# BLL-EBOOK.net
KiCad netlist of a schematic drawn in EAGLE
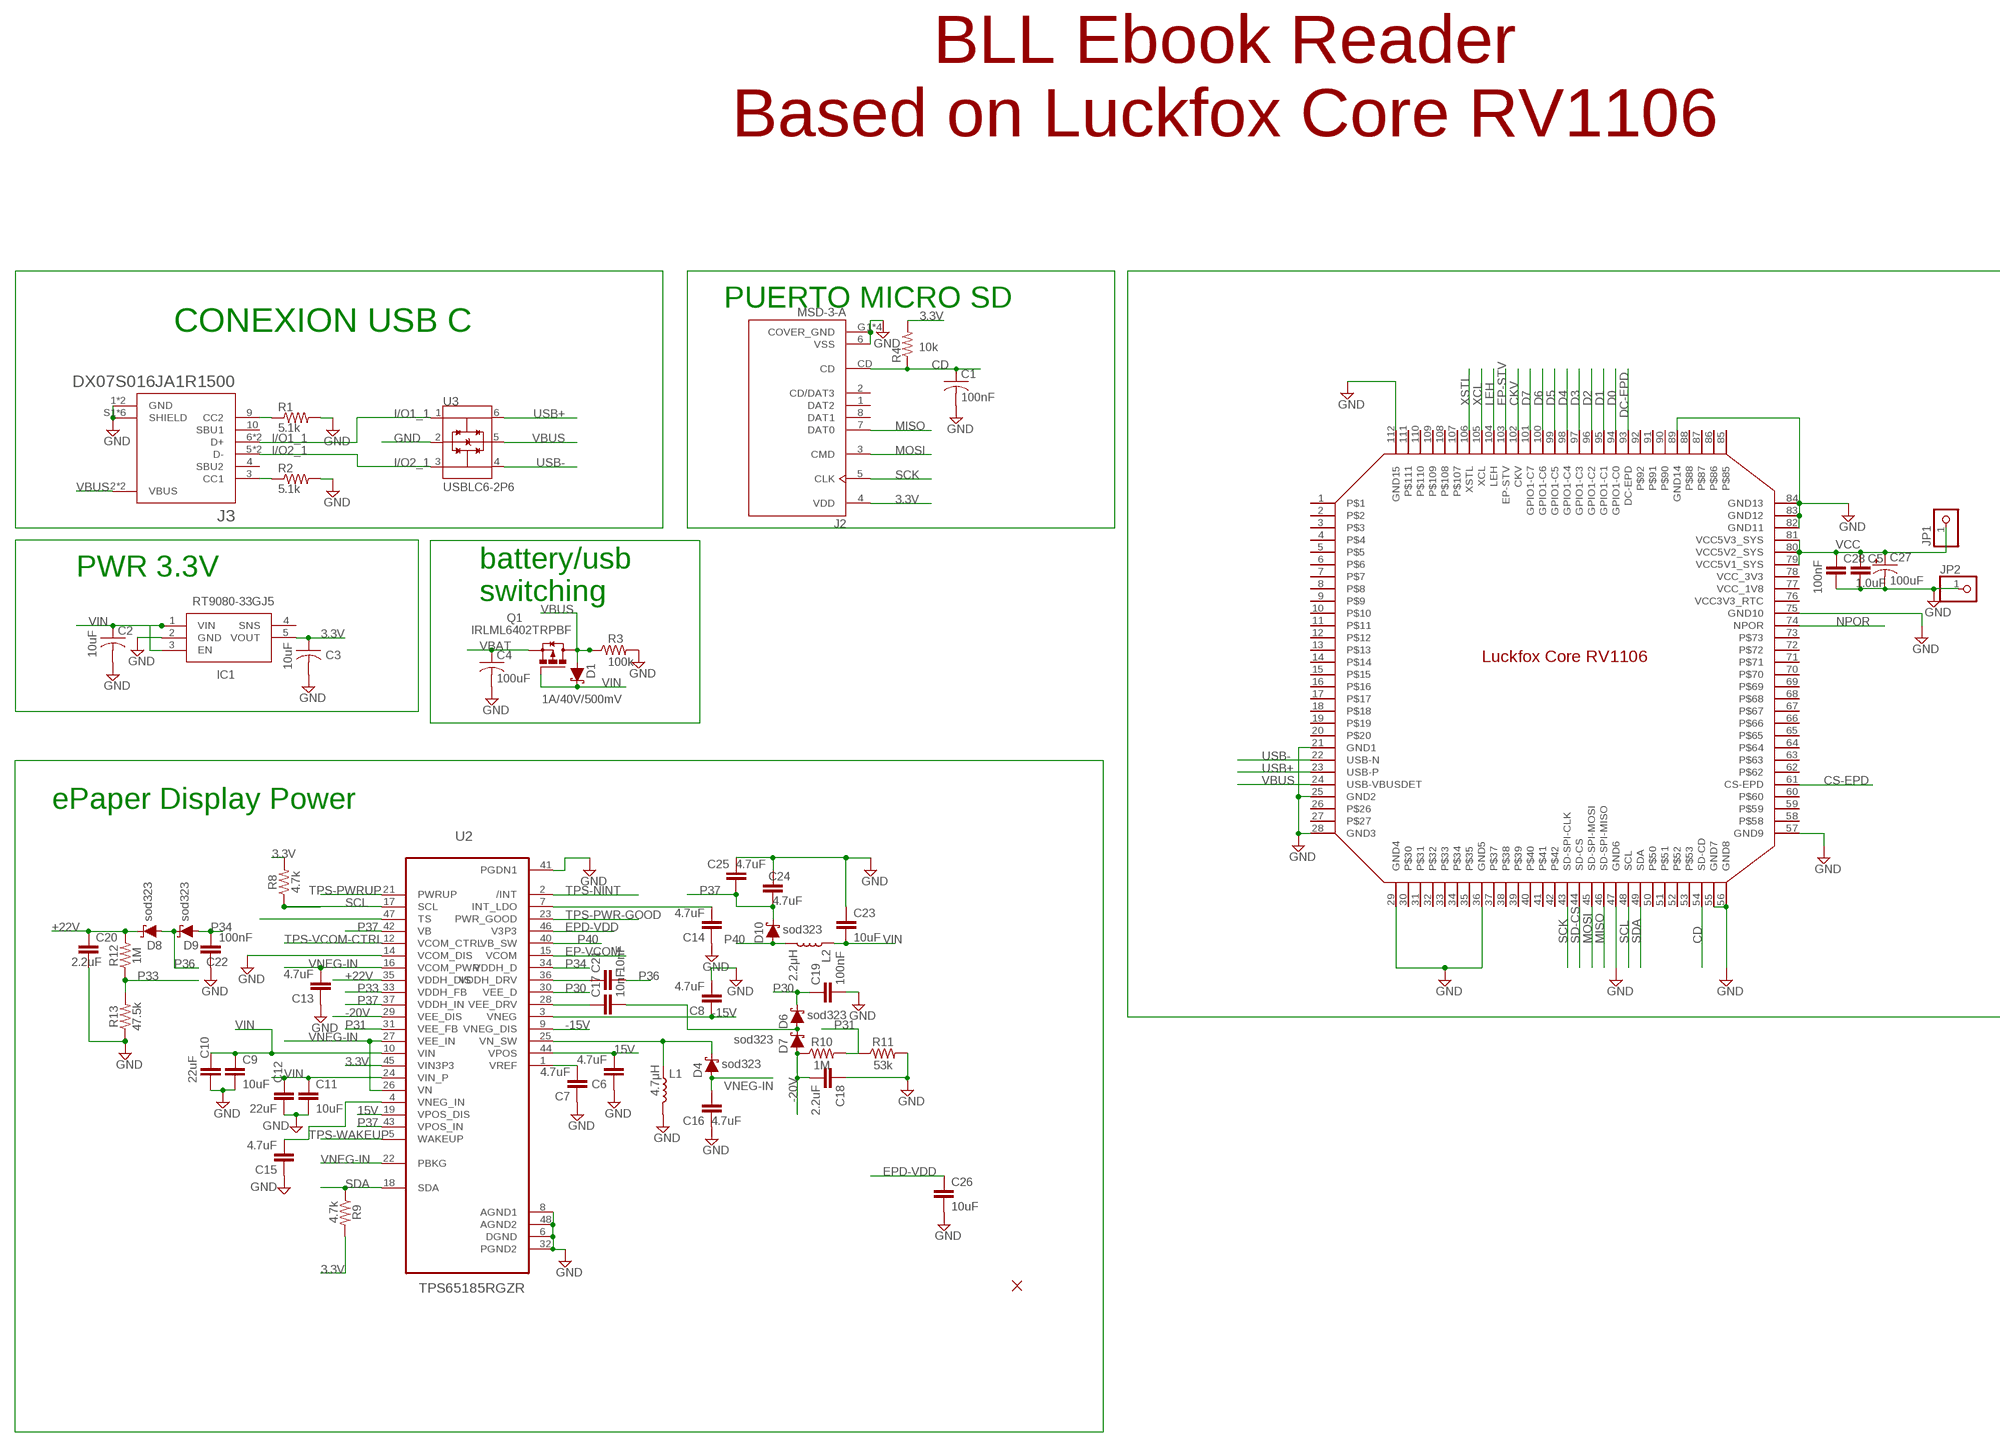
[diagram p0: schematic, sheet 1, part 1 of 2]
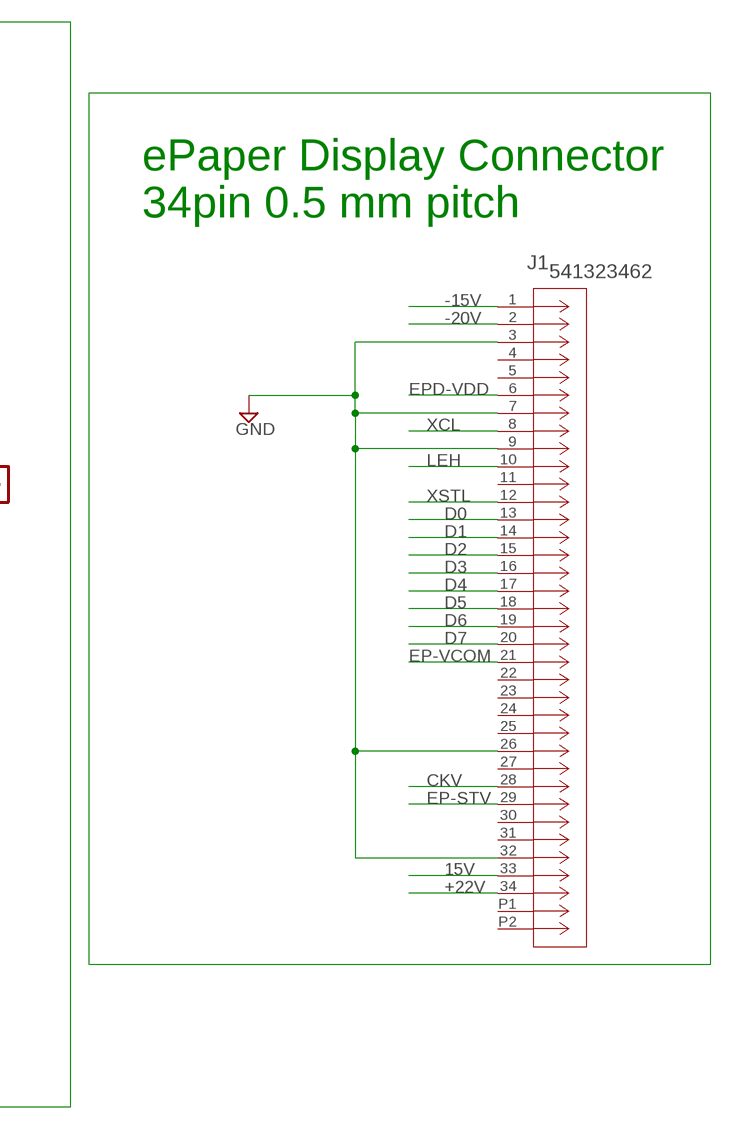
[diagram p1: schematic, sheet 1, part 2 of 2]

(export (version "E")
  (design (tool "Eeschema 10.0.6"))
  (components
    (comp (ref "C1")
      (value "100nF")
      (footprint "eagle-import:C0603")
      (libsource (lib "eagle-import") (part "C-USC0603"))
    )
    (comp (ref "C2")
      (value "10uF")
      (footprint "eagle-import:C0603")
      (libsource (lib "eagle-import") (part "C-USC0603"))
    )
    (comp (ref "C3")
      (value "10uF")
      (footprint "eagle-import:C0603")
      (libsource (lib "eagle-import") (part "C-USC0603"))
    )
    (comp (ref "C4")
      (value "100uF")
      (footprint "eagle-import:C0603")
      (libsource (lib "eagle-import") (part "C-USC0603"))
    )
    (comp (ref "C5")
      (value "1.0uF")
      (footprint "eagle-import:0603")
      (libsource (lib "eagle-import") (part "1.0UF-0603-16V-10%-X7R"))
    )
    (comp (ref "C6")
      (value "4.7uF")
      (footprint "eagle-import:0603")
      (libsource (lib "eagle-import") (part "4.7UF-0603-35V-(20%)"))
    )
    (comp (ref "C7")
      (value "4.7uF")
      (footprint "eagle-import:0603")
      (libsource (lib "eagle-import") (part "4.7UF-0603-35V-(20%)"))
    )
    (comp (ref "C8")
      (value "4.7uF")
      (footprint "eagle-import:0603")
      (libsource (lib "eagle-import") (part "4.7UF-0603-35V-(20%)"))
    )
    (comp (ref "C9")
      (value "10uF")
      (footprint "eagle-import:0805")
      (libsource (lib "eagle-import") (part "10UF-0805-10V-10%"))
    )
    (comp (ref "C10")
      (value "22uF")
      (footprint "eagle-import:0805")
      (libsource (lib "eagle-import") (part "22UF-0805-16V-20%"))
    )
    (comp (ref "C11")
      (value "10uF")
      (footprint "eagle-import:0805")
      (libsource (lib "eagle-import") (part "10UF-0805-10V-10%"))
    )
    (comp (ref "C12")
      (value "22uF")
      (footprint "eagle-import:0805")
      (libsource (lib "eagle-import") (part "22UF-0805-16V-20%"))
    )
    (comp (ref "C13")
      (value "4.7uF")
      (footprint "eagle-import:0603")
      (libsource (lib "eagle-import") (part "4.7UF-0603-35V-(20%)"))
    )
    (comp (ref "C14")
      (value "4.7uF")
      (footprint "eagle-import:0603")
      (libsource (lib "eagle-import") (part "4.7UF-0603-35V-(20%)"))
    )
    (comp (ref "C15")
      (value "4.7uF")
      (footprint "eagle-import:0603")
      (libsource (lib "eagle-import") (part "4.7UF-0603-35V-(20%)"))
    )
    (comp (ref "C16")
      (value "4.7uF")
      (footprint "eagle-import:0603")
      (libsource (lib "eagle-import") (part "4.7UF-0603-35V-(20%)"))
    )
    (comp (ref "C17")
      (value "10nF")
      (footprint "eagle-import:0603")
      (libsource (lib "eagle-import") (part "10NF-0603-50V-10%"))
    )
    (comp (ref "C18")
      (value "2.2uF")
      (footprint "eagle-import:1206")
      (libsource (lib "eagle-import") (part "2.2UF-1206-50V-10%"))
    )
    (comp (ref "C19")
      (value "100nF")
      (footprint "eagle-import:0603")
      (libsource (lib "eagle-import") (part "DNP-0603"))
    )
    (comp (ref "C20")
      (value "2.2uF")
      (footprint "eagle-import:1206")
      (libsource (lib "eagle-import") (part "2.2UF-1206-50V-10%"))
    )
    (comp (ref "C21")
      (value "10nF")
      (footprint "eagle-import:0603")
      (libsource (lib "eagle-import") (part "10NF-0603-50V-10%"))
    )
    (comp (ref "C22")
      (value "100nF")
      (footprint "eagle-import:0603")
      (libsource (lib "eagle-import") (part "DNP-0603"))
    )
    (comp (ref "C23")
      (value "10uF")
      (footprint "eagle-import:0805")
      (libsource (lib "eagle-import") (part "10UF-0805-10V-10%"))
    )
    (comp (ref "C24")
      (value "4.7uF")
      (footprint "eagle-import:0603")
      (libsource (lib "eagle-import") (part "4.7UF-0603-35V-(20%)"))
    )
    (comp (ref "C25")
      (value "4.7uF")
      (footprint "eagle-import:0603")
      (libsource (lib "eagle-import") (part "4.7UF-0603-35V-(20%)"))
    )
    (comp (ref "C26")
      (value "10uF")
      (footprint "eagle-import:0805")
      (libsource (lib "eagle-import") (part "10UF-0805-10V-10%"))
    )
    (comp (ref "C27")
      (value "100uF")
      (footprint "eagle-import:EIA3528")
      (libsource (lib "eagle-import") (part "100UF-POLAR-EIA3528-10V-20%(TANT)"))
    )
    (comp (ref "C28")
      (value "100nF")
      (footprint "eagle-import:0805")
      (libsource (lib "eagle-import") (part "CAP-0805"))
    )
    (comp (ref "D1")
      (value "1A/40V/500mV")
      (footprint "eagle-import:SMA-DIODE")
      (libsource (lib "eagle-import") (part "DIODE-SCHOTTKY-SS14"))
    )
    (comp (ref "D4")
      (value "sod323")
      (footprint "eagle-import:SOD-323")
      (libsource (lib "eagle-import") (part "DIODE-SCHOTTKY-PMEG4005EJ"))
    )
    (comp (ref "D6")
      (value "sod323")
      (footprint "eagle-import:SOD-323")
      (libsource (lib "eagle-import") (part "DIODE-SCHOTTKY-PMEG4005EJ"))
    )
    (comp (ref "D7")
      (value "sod323")
      (footprint "eagle-import:SOD-323")
      (libsource (lib "eagle-import") (part "DIODE-SCHOTTKY-PMEG4005EJ"))
    )
    (comp (ref "D8")
      (value "sod323")
      (footprint "eagle-import:SOD-323")
      (libsource (lib "eagle-import") (part "DIODE-SCHOTTKY-PMEG4005EJ"))
    )
    (comp (ref "D9")
      (value "sod323")
      (footprint "eagle-import:SOD-323")
      (libsource (lib "eagle-import") (part "DIODE-SCHOTTKY-PMEG4005EJ"))
    )
    (comp (ref "D10")
      (value "sod323")
      (footprint "eagle-import:SOD-323")
      (libsource (lib "eagle-import") (part "DIODE-SCHOTTKY-PMEG4005EJ"))
    )
    (comp (ref "IC1")
      (value "RT9080-33GJ5")
      (footprint "eagle-import:SOT94P280X100-5N")
      (fields (field (name "MF") "Richtek USA"))
      (libsource (lib "eagle-import") (part "RT9080-33GJ5"))
    )
    (comp (ref "J1")
      (value "541323462")
      (footprint "eagle-import:CON_541323462_MOL")
      (fields (field (name "MF") "Molex"))
      (libsource (lib "eagle-import") (part "541323462"))
    )
    (comp (ref "J2")
      (value "MSD-3-A")
      (footprint "eagle-import:CUI_MSD-3-A")
      (fields (field (name "MF") "Same Sky"))
      (libsource (lib "eagle-import") (part "MSD-3-A"))
    )
    (comp (ref "J3")
      (value "DX07S016JA1R1500")
      (footprint "eagle-import:JAE_DX07S016JA1R1500")
      (fields (field (name "MF") "JAE Electronics"))
      (libsource (lib "eagle-import") (part "DX07S016JA1R1500"))
    )
    (comp (ref "JP1")
      (value "PINHD-1X1")
      (footprint "eagle-import:1X01")
      (libsource (lib "eagle-import") (part "PINHD-1X1"))
    )
    (comp (ref "JP2")
      (value "PINHD-1X1")
      (footprint "eagle-import:1X01")
      (libsource (lib "eagle-import") (part "PINHD-1X1"))
    )
    (comp (ref "L1")
      (value "4.7μH")
      (footprint "eagle-import:1008(2520)")
      (libsource (lib "eagle-import") (part "4.7μH_SHIELDED_INDUCTOR"))
    )
    (comp (ref "L2")
      (value "2.2μH")
      (footprint "eagle-import:0806")
      (libsource (lib "eagle-import") (part "2.2μH_SHIELDED_INDUCTOR"))
    )
    (comp (ref "Q1")
      (value "IRLML6402TRPBF")
      (footprint "eagle-import:SOT23")
      (fields (field (name "MF") "Infineon Technologies") (field (name "MP") "IRLML6402"))
      (libsource (lib "eagle-import") (part "IRLML6402TRPBF"))
    )
    (comp (ref "R1")
      (value "5.1k")
      (footprint "eagle-import:M0805")
      (libsource (lib "eagle-import") (part "R-US_M0805"))
    )
    (comp (ref "R2")
      (value "5.1k")
      (footprint "eagle-import:M0805")
      (libsource (lib "eagle-import") (part "R-US_M0805"))
    )
    (comp (ref "R3")
      (value "100k")
      (footprint "eagle-import:R0603")
      (libsource (lib "eagle-import") (part "R-US_R0603"))
    )
    (comp (ref "R4")
      (value "10k")
      (footprint "eagle-import:M0805")
      (libsource (lib "eagle-import") (part "R-US_M0805"))
    )
    (comp (ref "R8")
      (value "4.7k")
      (footprint "eagle-import:0603")
      (libsource (lib "eagle-import") (part "4.7KOHM-0603-1/10W-1%"))
    )
    (comp (ref "R9")
      (value "4.7k")
      (footprint "eagle-import:0603")
      (libsource (lib "eagle-import") (part "4.7KOHM-0603-1/10W-1%"))
    )
    (comp (ref "R10")
      (value "1M")
      (footprint "eagle-import:0603")
      (libsource (lib "eagle-import") (part "1MOHM-0603-1/4W-5%"))
    )
    (comp (ref "R11")
      (value "53k")
      (footprint "eagle-import:0805")
      (libsource (lib "eagle-import") (part "RESISTOR0805"))
    )
    (comp (ref "R12")
      (value "1M")
      (footprint "eagle-import:0603")
      (libsource (lib "eagle-import") (part "1MOHM-0603-1/4W-5%"))
    )
    (comp (ref "R13")
      (value "47.5k")
      (footprint "eagle-import:0805")
      (libsource (lib "eagle-import") (part "RESISTOR0805"))
    )
    (comp (ref "U$1")
      (value "LUCKFOX_CORE_RV1106")
      (footprint "eagle-import:CORE1106-SMT")
      (fields (field (name "MF") "Luckfox Systems") (field (name "MP") "LuckFox Core1106"))
      (libsource (lib "eagle-import") (part "LUCKFOX_CORE_RV1106"))
    )
    (comp (ref "U2")
      (value "TPS65185RGZR")
      (footprint "eagle-import:QFN50P700X700X100-49N")
      (fields (field (name "MF") "Texas Instruments"))
      (libsource (lib "eagle-import") (part "TPS65185RGZR"))
    )
    (comp (ref "U3")
      (value "USBLC6-2P6")
      (footprint "eagle-import:SOT50P160X60-6N")
      (fields (field (name "MF") "STMicroelectronics"))
      (libsource (lib "eagle-import") (part "USBLC6-2P6"))
    )
  )
  (nets
    (net (code "1") (name "/+22V") (class "Default")
      (node (ref "C20") (pin "1") (pinfunction "1_1") (pintype "passive"))
      (node (ref "D8") (pin "C") (pinfunction "C_C") (pintype "passive"))
      (node (ref "J1") (pin "34") (pinfunction "34_34") (pintype "passive"))
      (node (ref "R12") (pin "2") (pinfunction "2_2") (pintype "passive"))
      (node (ref "U2") (pin "35") (pinfunction "VDDH_DIS_35") (pintype "input"))
    )
    (net (code "2") (name "/-15V") (class "Default")
      (node (ref "C8") (pin "1") (pinfunction "1_1") (pintype "passive"))
      (node (ref "J1") (pin "1") (pinfunction "1_1") (pintype "passive"))
      (node (ref "U2") (pin "3") (pinfunction "VNEG_3") (pintype "output"))
      (node (ref "U2") (pin "9") (pinfunction "VNEG_DIS_9") (pintype "output"))
    )
    (net (code "3") (name "/-20V") (class "Default")
      (node (ref "C18") (pin "2") (pinfunction "2_2") (pintype "passive"))
      (node (ref "D7") (pin "A") (pinfunction "A_A") (pintype "passive"))
      (node (ref "J1") (pin "2") (pinfunction "2_2") (pintype "passive"))
      (node (ref "R10") (pin "1") (pinfunction "1_1") (pintype "passive"))
      (node (ref "U2") (pin "29") (pinfunction "VEE_DIS_29") (pintype "input"))
    )
    (net (code "4") (name "/3.3V") (class "Default")
      (node (ref "C3") (pin "1") (pinfunction "1_1") (pintype "passive"))
      (node (ref "IC1") (pin "5") (pinfunction "VOUT_5") (pintype "bidirectional"))
      (node (ref "J2") (pin "4") (pinfunction "VDD_4") (pintype "power_in"))
      (node (ref "R4") (pin "2") (pinfunction "2_2") (pintype "passive"))
      (node (ref "R8") (pin "2") (pinfunction "2_2") (pintype "passive"))
      (node (ref "R9") (pin "2") (pinfunction "2_2") (pintype "passive"))
      (node (ref "U2") (pin "45") (pinfunction "VIN3P3_45") (pintype "input"))
    )
    (net (code "5") (name "/15V") (class "Default")
      (node (ref "C6") (pin "2") (pinfunction "2_2") (pintype "passive"))
      (node (ref "J1") (pin "33") (pinfunction "33_33") (pintype "passive"))
      (node (ref "U2") (pin "19") (pinfunction "VPOS_DIS_19") (pintype "input"))
      (node (ref "U2") (pin "44") (pinfunction "VPOS_44") (pintype "output"))
    )
    (net (code "6") (name "/CD") (class "Default")
      (node (ref "C1") (pin "1") (pinfunction "1_1") (pintype "passive"))
      (node (ref "J2") (pin "CD") (pinfunction "CD_CD") (pintype "passive"))
      (node (ref "R4") (pin "1") (pinfunction "1_1") (pintype "passive"))
      (node (ref "U$1") (pin "54") (pinfunction "SD-CD_54") (pintype "bidirectional"))
    )
    (net (code "7") (name "/CKV") (class "Default")
      (node (ref "J1") (pin "28") (pinfunction "28_28") (pintype "passive"))
      (node (ref "U$1") (pin "102") (pinfunction "CKV_102") (pintype "bidirectional"))
    )
    (net (code "8") (name "/CS-EPD") (class "Default")
      (node (ref "U$1") (pin "61") (pinfunction "CS-EPD_61") (pintype "bidirectional"))
    )
    (net (code "9") (name "/D0") (class "Default")
      (node (ref "J1") (pin "13") (pinfunction "13_13") (pintype "passive"))
      (node (ref "U$1") (pin "94") (pinfunction "GPIO1-C0_94") (pintype "bidirectional"))
    )
    (net (code "10") (name "/D1") (class "Default")
      (node (ref "J1") (pin "14") (pinfunction "14_14") (pintype "passive"))
      (node (ref "U$1") (pin "95") (pinfunction "GPIO1-C1_95") (pintype "bidirectional"))
    )
    (net (code "11") (name "/D2") (class "Default")
      (node (ref "J1") (pin "15") (pinfunction "15_15") (pintype "passive"))
      (node (ref "U$1") (pin "96") (pinfunction "GPIO1-C2_96") (pintype "bidirectional"))
    )
    (net (code "12") (name "/D3") (class "Default")
      (node (ref "J1") (pin "16") (pinfunction "16_16") (pintype "passive"))
      (node (ref "U$1") (pin "97") (pinfunction "GPIO1-C3_97") (pintype "bidirectional"))
    )
    (net (code "13") (name "/D4") (class "Default")
      (node (ref "J1") (pin "17") (pinfunction "17_17") (pintype "passive"))
      (node (ref "U$1") (pin "98") (pinfunction "GPIO1-C4_98") (pintype "bidirectional"))
    )
    (net (code "14") (name "/D5") (class "Default")
      (node (ref "J1") (pin "18") (pinfunction "18_18") (pintype "passive"))
      (node (ref "U$1") (pin "99") (pinfunction "GPIO1-C5_99") (pintype "bidirectional"))
    )
    (net (code "15") (name "/D6") (class "Default")
      (node (ref "J1") (pin "19") (pinfunction "19_19") (pintype "passive"))
      (node (ref "U$1") (pin "100") (pinfunction "GPIO1-C6_100") (pintype "bidirectional"))
    )
    (net (code "16") (name "/D7") (class "Default")
      (node (ref "J1") (pin "20") (pinfunction "20_20") (pintype "passive"))
      (node (ref "U$1") (pin "101") (pinfunction "GPIO1-C7_101") (pintype "bidirectional"))
    )
    (net (code "17") (name "/DC-EPD") (class "Default")
      (node (ref "U$1") (pin "93") (pinfunction "DC-EPD_93") (pintype "bidirectional"))
    )
    (net (code "18") (name "/EP-STV") (class "Default")
      (node (ref "J1") (pin "29") (pinfunction "29_29") (pintype "passive"))
      (node (ref "U$1") (pin "103") (pinfunction "EP-STV_103") (pintype "bidirectional"))
    )
    (net (code "19") (name "/EP-VCOM") (class "Default")
      (node (ref "J1") (pin "21") (pinfunction "21_21") (pintype "passive"))
      (node (ref "U2") (pin "15") (pinfunction "VCOM_15") (pintype "output"))
    )
    (net (code "20") (name "/EPD-VDD") (class "Default")
      (node (ref "C26") (pin "1") (pinfunction "1_1") (pintype "passive"))
      (node (ref "J1") (pin "6") (pinfunction "6_6") (pintype "passive"))
      (node (ref "U2") (pin "46") (pinfunction "V3P3_46") (pintype "output"))
    )
    (net (code "21") (name "/I{slash}O1_1") (class "Default")
      (node (ref "J3") (pin "6") (pinfunction "D+_6") (pintype "passive"))
      (node (ref "J3") (pin "7") (pinfunction "D+_7") (pintype "passive"))
      (node (ref "U3") (pin "1") (pinfunction "I/O1_1_1") (pintype "bidirectional"))
    )
    (net (code "22") (name "/I{slash}O2_1") (class "Default")
      (node (ref "J3") (pin "5") (pinfunction "D-_5") (pintype "passive"))
      (node (ref "J3") (pin "8") (pinfunction "D-_8") (pintype "passive"))
      (node (ref "U3") (pin "3") (pinfunction "I/O2_1_3") (pintype "bidirectional"))
    )
    (net (code "23") (name "/LEH") (class "Default")
      (node (ref "J1") (pin "10") (pinfunction "10_10") (pintype "passive"))
      (node (ref "U$1") (pin "104") (pinfunction "LEH_104") (pintype "bidirectional"))
    )
    (net (code "24") (name "/MISO") (class "Default")
      (node (ref "J2") (pin "7") (pinfunction "DAT0_7") (pintype "bidirectional"))
      (node (ref "U$1") (pin "46") (pinfunction "SD-SPI-MISO_46") (pintype "bidirectional"))
    )
    (net (code "25") (name "/MOSI") (class "Default")
      (node (ref "J2") (pin "3") (pinfunction "CMD_3") (pintype "bidirectional"))
      (node (ref "U$1") (pin "45") (pinfunction "SD-SPI-MOSI_45") (pintype "bidirectional"))
    )
    (net (code "26") (name "/NPOR") (class "Default")
      (node (ref "U$1") (pin "74") (pinfunction "NPOR_74") (pintype "bidirectional"))
    )
    (net (code "27") (name "/P30") (class "Default")
      (node (ref "C19") (pin "1") (pinfunction "1_1") (pintype "passive"))
      (node (ref "D6") (pin "C") (pinfunction "C_C") (pintype "passive"))
      (node (ref "U2") (pin "30") (pinfunction "VEE_D_30") (pintype "output"))
    )
    (net (code "28") (name "/P31") (class "Default")
      (node (ref "R10") (pin "2") (pinfunction "2_2") (pintype "passive"))
      (node (ref "R11") (pin "1") (pinfunction "1_1") (pintype "passive"))
      (node (ref "U2") (pin "31") (pinfunction "VEE_FB_31") (pintype "input"))
    )
    (net (code "29") (name "/P33") (class "Default")
      (node (ref "R12") (pin "1") (pinfunction "1_1") (pintype "passive"))
      (node (ref "R13") (pin "2") (pinfunction "2_2") (pintype "passive"))
      (node (ref "U2") (pin "33") (pinfunction "VDDH_FB_33") (pintype "input"))
    )
    (net (code "30") (name "/P34") (class "Default")
      (node (ref "C22") (pin "2") (pinfunction "2_2") (pintype "passive"))
      (node (ref "D9") (pin "A") (pinfunction "A_A") (pintype "passive"))
      (node (ref "U2") (pin "34") (pinfunction "VDDH_D_34") (pintype "output"))
    )
    (net (code "31") (name "/P36") (class "Default")
      (node (ref "C21") (pin "2") (pinfunction "2_2") (pintype "passive"))
      (node (ref "D8") (pin "A") (pinfunction "A_A") (pintype "passive"))
      (node (ref "D9") (pin "C") (pinfunction "C_C") (pintype "passive"))
    )
    (net (code "32") (name "/P37") (class "Default")
      (node (ref "C24") (pin "1") (pinfunction "1_1") (pintype "passive"))
      (node (ref "C25") (pin "1") (pinfunction "1_1") (pintype "passive"))
      (node (ref "D10") (pin "C") (pinfunction "C_C") (pintype "passive"))
      (node (ref "U2") (pin "37") (pinfunction "VDDH_IN_37") (pintype "input"))
      (node (ref "U2") (pin "42") (pinfunction "VB_42") (pintype "input"))
      (node (ref "U2") (pin "43") (pinfunction "VPOS_IN_43") (pintype "input"))
    )
    (net (code "33") (name "/P40") (class "Default")
      (node (ref "D10") (pin "A") (pinfunction "A_A") (pintype "passive"))
      (node (ref "L2") (pin "2") (pinfunction "2_2") (pintype "passive"))
      (node (ref "U2") (pin "40") (pinfunction "VB_SW_40") (pintype "output"))
    )
    (net (code "34") (name "/SCK") (class "Default")
      (node (ref "J2") (pin "5") (pinfunction "CLK_5") (pintype "input"))
      (node (ref "U$1") (pin "43") (pinfunction "SD-SPI-CLK_43") (pintype "bidirectional"))
    )
    (net (code "35") (name "/SCL") (class "Default")
      (node (ref "R8") (pin "1") (pinfunction "1_1") (pintype "passive"))
      (node (ref "U$1") (pin "48") (pinfunction "SCL_48") (pintype "bidirectional"))
      (node (ref "U2") (pin "17") (pinfunction "SCL_17") (pintype "input"))
    )
    (net (code "36") (name "/SD-CS") (class "Default")
      (node (ref "U$1") (pin "44") (pinfunction "SD-CS_44") (pintype "bidirectional"))
    )
    (net (code "37") (name "/SDA") (class "Default")
      (node (ref "R9") (pin "1") (pinfunction "1_1") (pintype "passive"))
      (node (ref "U$1") (pin "49") (pinfunction "SDA_49") (pintype "bidirectional"))
      (node (ref "U2") (pin "18") (pinfunction "SDA_18") (pintype "bidirectional"))
    )
    (net (code "38") (name "/TPS-NINT") (class "Default")
      (node (ref "U2") (pin "2") (pinfunction "/INT_2") (pintype "output"))
    )
    (net (code "39") (name "/TPS-PWR-GOOD") (class "Default")
      (node (ref "U2") (pin "23") (pinfunction "PWR_GOOD_23") (pintype "output"))
    )
    (net (code "40") (name "/TPS-PWRUP") (class "Default")
      (node (ref "U2") (pin "21") (pinfunction "PWRUP_21") (pintype "input"))
    )
    (net (code "41") (name "/TPS-VCOM-CTRL") (class "Default")
      (node (ref "U2") (pin "12") (pinfunction "VCOM_CTRL_12") (pintype "input"))
    )
    (net (code "42") (name "/TPS-WAKEUP") (class "Default")
      (node (ref "U2") (pin "5") (pinfunction "WAKEUP_5") (pintype "input"))
    )
    (net (code "43") (name "/USB+") (class "Default")
      (node (ref "U$1") (pin "23") (pinfunction "USB-P_23") (pintype "bidirectional"))
      (node (ref "U3") (pin "6") (pinfunction "I/O1_2_6") (pintype "bidirectional"))
    )
    (net (code "44") (name "/USB-") (class "Default")
      (node (ref "U$1") (pin "22") (pinfunction "USB-N_22") (pintype "bidirectional"))
      (node (ref "U3") (pin "4") (pinfunction "I/O2_2_4") (pintype "bidirectional"))
    )
    (net (code "45") (name "/VBAT") (class "Default")
      (node (ref "C4") (pin "1") (pinfunction "1_1") (pintype "passive"))
      (node (ref "Q1") (pin "2") (pinfunction "S_2") (pintype "passive"))
    )
    (net (code "46") (name "/VBUS") (class "Default")
      (node (ref "D1") (pin "A") (pinfunction "A_A") (pintype "passive"))
      (node (ref "J3") (pin "11") (pinfunction "VBUS_11") (pintype "power_in"))
      (node (ref "J3") (pin "2") (pinfunction "VBUS_2") (pintype "power_in"))
      (node (ref "Q1") (pin "3") (pinfunction "D_3") (pintype "passive"))
      (node (ref "R3") (pin "1") (pinfunction "1_1") (pintype "passive"))
      (node (ref "U$1") (pin "24") (pinfunction "USB-VBUSDET_24") (pintype "bidirectional"))
      (node (ref "U3") (pin "5") (pinfunction "VBUS_5") (pintype "power_in"))
    )
    (net (code "47") (name "/VCC") (class "Default")
      (node (ref "C27") (pin "A") (pinfunction "+_A") (pintype "passive"))
      (node (ref "C28") (pin "1") (pinfunction "1_1") (pintype "passive"))
      (node (ref "C5") (pin "1") (pinfunction "1_1") (pintype "passive"))
      (node (ref "JP1") (pin "1") (pinfunction "1_1") (pintype "passive"))
      (node (ref "U$1") (pin "79") (pinfunction "VCC5V1_SYS_79") (pintype "power_in"))
      (node (ref "U$1") (pin "80") (pinfunction "VCC5V2_SYS_80") (pintype "bidirectional"))
      (node (ref "U$1") (pin "81") (pinfunction "VCC5V3_SYS_81") (pintype "bidirectional"))
    )
    (net (code "48") (name "/VCC3V3_RTC") (class "Default")
      (node (ref "U$1") (pin "76") (pinfunction "VCC3V3_RTC_76") (pintype "power_in"))
    )
    (net (code "49") (name "/VIN") (class "Default")
      (node (ref "C10") (pin "1") (pinfunction "1_1") (pintype "passive"))
      (node (ref "C11") (pin "1") (pinfunction "1_1") (pintype "passive"))
      (node (ref "C12") (pin "1") (pinfunction "1_1") (pintype "passive"))
      (node (ref "C2") (pin "1") (pinfunction "1_1") (pintype "passive"))
      (node (ref "C23") (pin "2") (pinfunction "2_2") (pintype "passive"))
      (node (ref "C9") (pin "1") (pinfunction "1_1") (pintype "passive"))
      (node (ref "D1") (pin "C") (pinfunction "C_C") (pintype "passive"))
      (node (ref "IC1") (pin "1") (pinfunction "VIN_1") (pintype "bidirectional"))
      (node (ref "IC1") (pin "3") (pinfunction "EN_3") (pintype "bidirectional"))
      (node (ref "L2") (pin "1") (pinfunction "1_1") (pintype "passive"))
      (node (ref "Q1") (pin "1") (pinfunction "G_1") (pintype "passive"))
      (node (ref "U2") (pin "10") (pinfunction "VIN_10") (pintype "input"))
      (node (ref "U2") (pin "24") (pinfunction "VIN_P_24") (pintype "input"))
    )
    (net (code "50") (name "/VNEG-IN") (class "Default")
      (node (ref "C13") (pin "2") (pinfunction "2_2") (pintype "passive"))
      (node (ref "C16") (pin "2") (pinfunction "2_2") (pintype "passive"))
      (node (ref "D4") (pin "A") (pinfunction "A_A") (pintype "passive"))
      (node (ref "U2") (pin "16") (pinfunction "VCOM_PWR_16") (pintype "input"))
      (node (ref "U2") (pin "22") (pinfunction "PBKG_22") (pintype "bidirectional"))
      (node (ref "U2") (pin "26") (pinfunction "VN_26") (pintype "input"))
      (node (ref "U2") (pin "27") (pinfunction "VEE_IN_27") (pintype "input"))
    )
    (net (code "51") (name "/XCL") (class "Default")
      (node (ref "J1") (pin "8") (pinfunction "8_8") (pintype "passive"))
      (node (ref "U$1") (pin "105") (pinfunction "XCL_105") (pintype "bidirectional"))
    )
    (net (code "52") (name "/XSTL") (class "Default")
      (node (ref "J1") (pin "12") (pinfunction "12_12") (pintype "passive"))
      (node (ref "U$1") (pin "106") (pinfunction "XSTL_106") (pintype "bidirectional"))
    )
    (net (code "53") (name "GND") (class "Default")
      (node (ref "C1") (pin "2") (pinfunction "2_2") (pintype "passive"))
      (node (ref "C10") (pin "2") (pinfunction "2_2") (pintype "passive"))
      (node (ref "C11") (pin "2") (pinfunction "2_2") (pintype "passive"))
      (node (ref "C12") (pin "2") (pinfunction "2_2") (pintype "passive"))
      (node (ref "C13") (pin "1") (pinfunction "1_1") (pintype "passive"))
      (node (ref "C14") (pin "1") (pinfunction "1_1") (pintype "passive"))
      (node (ref "C15") (pin "1") (pinfunction "1_1") (pintype "passive"))
      (node (ref "C16") (pin "1") (pinfunction "1_1") (pintype "passive"))
      (node (ref "C18") (pin "1") (pinfunction "1_1") (pintype "passive"))
      (node (ref "C19") (pin "2") (pinfunction "2_2") (pintype "passive"))
      (node (ref "C2") (pin "2") (pinfunction "2_2") (pintype "passive"))
      (node (ref "C20") (pin "2") (pinfunction "2_2") (pintype "passive"))
      (node (ref "C22") (pin "1") (pinfunction "1_1") (pintype "passive"))
      (node (ref "C23") (pin "1") (pinfunction "1_1") (pintype "passive"))
      (node (ref "C24") (pin "2") (pinfunction "2_2") (pintype "passive"))
      (node (ref "C25") (pin "2") (pinfunction "2_2") (pintype "passive"))
      (node (ref "C26") (pin "2") (pinfunction "2_2") (pintype "passive"))
      (node (ref "C27") (pin "C") (pinfunction "-_C") (pintype "passive"))
      (node (ref "C28") (pin "2") (pinfunction "2_2") (pintype "passive"))
      (node (ref "C3") (pin "2") (pinfunction "2_2") (pintype "passive"))
      (node (ref "C4") (pin "2") (pinfunction "2_2") (pintype "passive"))
      (node (ref "C5") (pin "2") (pinfunction "2_2") (pintype "passive"))
      (node (ref "C6") (pin "1") (pinfunction "1_1") (pintype "passive"))
      (node (ref "C7") (pin "1") (pinfunction "1_1") (pintype "passive"))
      (node (ref "C8") (pin "2") (pinfunction "2_2") (pintype "passive"))
      (node (ref "C9") (pin "2") (pinfunction "2_2") (pintype "passive"))
      (node (ref "IC1") (pin "2") (pinfunction "GND_2") (pintype "bidirectional"))
      (node (ref "J1") (pin "26") (pinfunction "26_26") (pintype "passive"))
      (node (ref "J1") (pin "3") (pinfunction "3_3") (pintype "passive"))
      (node (ref "J1") (pin "32") (pinfunction "32_32") (pintype "passive"))
      (node (ref "J1") (pin "7") (pinfunction "7_7") (pintype "passive"))
      (node (ref "J1") (pin "9") (pinfunction "9_9") (pintype "passive"))
      (node (ref "J2") (pin "6") (pinfunction "VSS_6") (pintype "power_in"))
      (node (ref "J2") (pin "G1") (pinfunction "COVER_GND_G1") (pintype "power_in"))
      (node (ref "J2") (pin "G2") (pinfunction "COVER_GND_G2") (pintype "power_in"))
      (node (ref "J2") (pin "G3") (pinfunction "COVER_GND_G3") (pintype "power_in"))
      (node (ref "J2") (pin "G4") (pinfunction "COVER_GND_G4") (pintype "power_in"))
      (node (ref "J3") (pin "1") (pinfunction "GND_1") (pintype "power_in"))
      (node (ref "J3") (pin "12") (pinfunction "GND_12") (pintype "power_in"))
      (node (ref "J3") (pin "S1") (pinfunction "SHIELD_S1") (pintype "passive"))
      (node (ref "J3") (pin "S2") (pinfunction "SHIELD_S2") (pintype "passive"))
      (node (ref "J3") (pin "S3") (pinfunction "SHIELD_S3") (pintype "passive"))
      (node (ref "J3") (pin "S4") (pinfunction "SHIELD_S4") (pintype "passive"))
      (node (ref "J3") (pin "S5") (pinfunction "SHIELD_S5") (pintype "passive"))
      (node (ref "J3") (pin "S6") (pinfunction "SHIELD_S6") (pintype "passive"))
      (node (ref "JP2") (pin "1") (pinfunction "1_1") (pintype "passive"))
      (node (ref "L1") (pin "2") (pinfunction "2_2") (pintype "passive"))
      (node (ref "R1") (pin "2") (pinfunction "2_2") (pintype "passive"))
      (node (ref "R11") (pin "2") (pinfunction "2_2") (pintype "passive"))
      (node (ref "R13") (pin "1") (pinfunction "1_1") (pintype "passive"))
      (node (ref "R2") (pin "2") (pinfunction "2_2") (pintype "passive"))
      (node (ref "R3") (pin "2") (pinfunction "2_2") (pintype "passive"))
      (node (ref "U$1") (pin "112") (pinfunction "GND15_112") (pintype "bidirectional"))
      (node (ref "U$1") (pin "21") (pinfunction "GND1_21") (pintype "bidirectional"))
      (node (ref "U$1") (pin "25") (pinfunction "GND2_25") (pintype "output"))
      (node (ref "U$1") (pin "28") (pinfunction "GND3_28") (pintype "bidirectional"))
      (node (ref "U$1") (pin "29") (pinfunction "GND4_29") (pintype "bidirectional"))
      (node (ref "U$1") (pin "36") (pinfunction "GND5_36") (pintype "bidirectional"))
      (node (ref "U$1") (pin "47") (pinfunction "GND6_47") (pintype "bidirectional"))
      (node (ref "U$1") (pin "55") (pinfunction "GND7_55") (pintype "bidirectional"))
      (node (ref "U$1") (pin "56") (pinfunction "GND8_56") (pintype "bidirectional"))
      (node (ref "U$1") (pin "57") (pinfunction "GND9_57") (pintype "bidirectional"))
      (node (ref "U$1") (pin "75") (pinfunction "GND10_75") (pintype "bidirectional"))
      (node (ref "U$1") (pin "82") (pinfunction "GND11_82") (pintype "bidirectional"))
      (node (ref "U$1") (pin "83") (pinfunction "GND12_83") (pintype "bidirectional"))
      (node (ref "U$1") (pin "84") (pinfunction "GND13_84") (pintype "bidirectional"))
      (node (ref "U$1") (pin "89") (pinfunction "GND14_89") (pintype "bidirectional"))
      (node (ref "U2") (pin "14") (pinfunction "VCOM_DIS_14") (pintype "input"))
      (node (ref "U2") (pin "32") (pinfunction "PGND2_32") (pintype "power_in"))
      (node (ref "U2") (pin "41") (pinfunction "PGDN1_41") (pintype "power_in"))
      (node (ref "U2") (pin "48") (pinfunction "AGND2_48") (pintype "power_in"))
      (node (ref "U2") (pin "6") (pinfunction "DGND_6") (pintype "power_in"))
      (node (ref "U2") (pin "8") (pinfunction "AGND1_8") (pintype "power_in"))
      (node (ref "U3") (pin "2") (pinfunction "GND_2") (pintype "power_in"))
    )
    (net (code "54") (name "Net-(C17-Pad2)") (class "Default")
      (node (ref "C17") (pin "2") (pinfunction "2_2") (pintype "passive"))
      (node (ref "D6") (pin "A") (pinfunction "A_A") (pintype "passive"))
      (node (ref "D7") (pin "C") (pinfunction "C_C") (pintype "passive"))
    )
    (net (code "55") (name "Net-(J3-CC1)") (class "Default")
      (node (ref "J3") (pin "3") (pinfunction "CC1_3") (pintype "passive"))
      (node (ref "R2") (pin "1") (pinfunction "1_1") (pintype "passive"))
    )
    (net (code "56") (name "Net-(J3-CC2)") (class "Default")
      (node (ref "J3") (pin "9") (pinfunction "CC2_9") (pintype "passive"))
      (node (ref "R1") (pin "1") (pinfunction "1_1") (pintype "passive"))
    )
    (net (code "57") (name "Net-(U2-INT_LDO)") (class "Default")
      (node (ref "C14") (pin "2") (pinfunction "2_2") (pintype "passive"))
      (node (ref "U2") (pin "7") (pinfunction "INT_LDO_7") (pintype "output"))
    )
    (net (code "58") (name "Net-(U2-VDDH_DRV)") (class "Default")
      (node (ref "C21") (pin "1") (pinfunction "1_1") (pintype "passive"))
      (node (ref "U2") (pin "36") (pinfunction "VDDH_DRV_36") (pintype "output"))
    )
    (net (code "59") (name "Net-(U2-VEE_DRV)") (class "Default")
      (node (ref "C17") (pin "1") (pinfunction "1_1") (pintype "passive"))
      (node (ref "U2") (pin "28") (pinfunction "VEE_DRV_28") (pintype "output"))
    )
    (net (code "60") (name "Net-(U2-VNEG_IN)") (class "Default")
      (node (ref "C15") (pin "2") (pinfunction "2_2") (pintype "passive"))
      (node (ref "U2") (pin "4") (pinfunction "VNEG_IN_4") (pintype "input"))
    )
    (net (code "61") (name "Net-(U2-VN_SW)") (class "Default")
      (node (ref "D4") (pin "C") (pinfunction "C_C") (pintype "passive"))
      (node (ref "L1") (pin "1") (pinfunction "1_1") (pintype "passive"))
      (node (ref "U2") (pin "25") (pinfunction "VN_SW_25") (pintype "output"))
    )
    (net (code "62") (name "Net-(U2-VREF)") (class "Default")
      (node (ref "C7") (pin "2") (pinfunction "2_2") (pintype "passive"))
      (node (ref "U2") (pin "1") (pinfunction "VREF_1") (pintype "output"))
    )
    (net (code "63") (name "unconnected-(IC1-SNS-Pad4)") (class "Default")
      (node (ref "IC1") (pin "4") (pinfunction "SNS_4") (pintype "bidirectional"))
    )
    (net (code "64") (name "unconnected-(J1-Pad4)") (class "Default")
      (node (ref "J1") (pin "4") (pinfunction "4_4") (pintype "passive"))
    )
    (net (code "65") (name "unconnected-(J1-Pad5)") (class "Default")
      (node (ref "J1") (pin "5") (pinfunction "5_5") (pintype "passive"))
    )
    (net (code "66") (name "unconnected-(J1-Pad11)") (class "Default")
      (node (ref "J1") (pin "11") (pinfunction "11_11") (pintype "passive"))
    )
    (net (code "67") (name "unconnected-(J1-Pad22)") (class "Default")
      (node (ref "J1") (pin "22") (pinfunction "22_22") (pintype "passive"))
    )
    (net (code "68") (name "unconnected-(J1-Pad23)") (class "Default")
      (node (ref "J1") (pin "23") (pinfunction "23_23") (pintype "passive"))
    )
    (net (code "69") (name "unconnected-(J1-Pad24)") (class "Default")
      (node (ref "J1") (pin "24") (pinfunction "24_24") (pintype "passive"))
    )
    (net (code "70") (name "unconnected-(J1-Pad25)") (class "Default")
      (node (ref "J1") (pin "25") (pinfunction "25_25") (pintype "passive"))
    )
    (net (code "71") (name "unconnected-(J1-Pad27)") (class "Default")
      (node (ref "J1") (pin "27") (pinfunction "27_27") (pintype "passive"))
    )
    (net (code "72") (name "unconnected-(J1-Pad30)") (class "Default")
      (node (ref "J1") (pin "30") (pinfunction "30_30") (pintype "passive"))
    )
    (net (code "73") (name "unconnected-(J1-Pad31)") (class "Default")
      (node (ref "J1") (pin "31") (pinfunction "31_31") (pintype "passive"))
    )
    (net (code "74") (name "unconnected-(J1-PadP1)") (class "Default")
      (node (ref "J1") (pin "P1") (pinfunction "P1_P1") (pintype "passive"))
    )
    (net (code "75") (name "unconnected-(J1-PadP2)") (class "Default")
      (node (ref "J1") (pin "P2") (pinfunction "P2_P2") (pintype "passive"))
    )
    (net (code "76") (name "unconnected-(J2-CD{slash}DAT3-Pad2)") (class "Default")
      (node (ref "J2") (pin "2") (pinfunction "CD/DAT3_2") (pintype "bidirectional"))
    )
    (net (code "77") (name "unconnected-(J2-DAT1-Pad8)") (class "Default")
      (node (ref "J2") (pin "8") (pinfunction "DAT1_8") (pintype "bidirectional"))
    )
    (net (code "78") (name "unconnected-(J2-DAT2-Pad1)") (class "Default")
      (node (ref "J2") (pin "1") (pinfunction "DAT2_1") (pintype "bidirectional"))
    )
    (net (code "79") (name "unconnected-(J3-SBU1-Pad10)") (class "Default")
      (node (ref "J3") (pin "10") (pinfunction "SBU1_10") (pintype "passive"))
    )
    (net (code "80") (name "unconnected-(J3-SBU2-Pad4)") (class "Default")
      (node (ref "J3") (pin "4") (pinfunction "SBU2_4") (pintype "passive"))
    )
    (net (code "81") (name "unconnected-(U$1-P$1-Pad1)") (class "Default")
      (node (ref "U$1") (pin "1") (pinfunction "P$1_1") (pintype "bidirectional"))
    )
    (net (code "82") (name "unconnected-(U$1-P$2-Pad2)") (class "Default")
      (node (ref "U$1") (pin "2") (pinfunction "P$2_2") (pintype "bidirectional"))
    )
    (net (code "83") (name "unconnected-(U$1-P$3-Pad3)") (class "Default")
      (node (ref "U$1") (pin "3") (pinfunction "P$3_3") (pintype "bidirectional"))
    )
    (net (code "84") (name "unconnected-(U$1-P$4-Pad4)") (class "Default")
      (node (ref "U$1") (pin "4") (pinfunction "P$4_4") (pintype "bidirectional"))
    )
    (net (code "85") (name "unconnected-(U$1-P$5-Pad5)") (class "Default")
      (node (ref "U$1") (pin "5") (pinfunction "P$5_5") (pintype "bidirectional"))
    )
    (net (code "86") (name "unconnected-(U$1-P$6-Pad6)") (class "Default")
      (node (ref "U$1") (pin "6") (pinfunction "P$6_6") (pintype "bidirectional"))
    )
    (net (code "87") (name "unconnected-(U$1-P$7-Pad7)") (class "Default")
      (node (ref "U$1") (pin "7") (pinfunction "P$7_7") (pintype "bidirectional"))
    )
    (net (code "88") (name "unconnected-(U$1-P$8-Pad8)") (class "Default")
      (node (ref "U$1") (pin "8") (pinfunction "P$8_8") (pintype "bidirectional"))
    )
    (net (code "89") (name "unconnected-(U$1-P$9-Pad9)") (class "Default")
      (node (ref "U$1") (pin "9") (pinfunction "P$9_9") (pintype "bidirectional"))
    )
    (net (code "90") (name "unconnected-(U$1-P$10-Pad10)") (class "Default")
      (node (ref "U$1") (pin "10") (pinfunction "P$10_10") (pintype "bidirectional"))
    )
    (net (code "91") (name "unconnected-(U$1-P$11-Pad11)") (class "Default")
      (node (ref "U$1") (pin "11") (pinfunction "P$11_11") (pintype "bidirectional"))
    )
    (net (code "92") (name "unconnected-(U$1-P$12-Pad12)") (class "Default")
      (node (ref "U$1") (pin "12") (pinfunction "P$12_12") (pintype "bidirectional"))
    )
    (net (code "93") (name "unconnected-(U$1-P$13-Pad13)") (class "Default")
      (node (ref "U$1") (pin "13") (pinfunction "P$13_13") (pintype "bidirectional"))
    )
    (net (code "94") (name "unconnected-(U$1-P$14-Pad14)") (class "Default")
      (node (ref "U$1") (pin "14") (pinfunction "P$14_14") (pintype "bidirectional"))
    )
    (net (code "95") (name "unconnected-(U$1-P$15-Pad15)") (class "Default")
      (node (ref "U$1") (pin "15") (pinfunction "P$15_15") (pintype "bidirectional"))
    )
    (net (code "96") (name "unconnected-(U$1-P$16-Pad16)") (class "Default")
      (node (ref "U$1") (pin "16") (pinfunction "P$16_16") (pintype "bidirectional"))
    )
    (net (code "97") (name "unconnected-(U$1-P$17-Pad17)") (class "Default")
      (node (ref "U$1") (pin "17") (pinfunction "P$17_17") (pintype "bidirectional"))
    )
    (net (code "98") (name "unconnected-(U$1-P$18-Pad18)") (class "Default")
      (node (ref "U$1") (pin "18") (pinfunction "P$18_18") (pintype "bidirectional"))
    )
    (net (code "99") (name "unconnected-(U$1-P$19-Pad19)") (class "Default")
      (node (ref "U$1") (pin "19") (pinfunction "P$19_19") (pintype "bidirectional"))
    )
    (net (code "100") (name "unconnected-(U$1-P$20-Pad20)") (class "Default")
      (node (ref "U$1") (pin "20") (pinfunction "P$20_20") (pintype "bidirectional"))
    )
    (net (code "101") (name "unconnected-(U$1-P$26-Pad26)") (class "Default")
      (node (ref "U$1") (pin "26") (pinfunction "P$26_26") (pintype "bidirectional"))
    )
    (net (code "102") (name "unconnected-(U$1-P$27-Pad27)") (class "Default")
      (node (ref "U$1") (pin "27") (pinfunction "P$27_27") (pintype "bidirectional"))
    )
    (net (code "103") (name "unconnected-(U$1-P$30-Pad30)") (class "Default")
      (node (ref "U$1") (pin "30") (pinfunction "P$30_30") (pintype "bidirectional"))
    )
    (net (code "104") (name "unconnected-(U$1-P$31-Pad31)") (class "Default")
      (node (ref "U$1") (pin "31") (pinfunction "P$31_31") (pintype "bidirectional"))
    )
    (net (code "105") (name "unconnected-(U$1-P$32-Pad32)") (class "Default")
      (node (ref "U$1") (pin "32") (pinfunction "P$32_32") (pintype "bidirectional"))
    )
    (net (code "106") (name "unconnected-(U$1-P$33-Pad33)") (class "Default")
      (node (ref "U$1") (pin "33") (pinfunction "P$33_33") (pintype "bidirectional"))
    )
    (net (code "107") (name "unconnected-(U$1-P$34-Pad34)") (class "Default")
      (node (ref "U$1") (pin "34") (pinfunction "P$34_34") (pintype "bidirectional"))
    )
    (net (code "108") (name "unconnected-(U$1-P$35-Pad35)") (class "Default")
      (node (ref "U$1") (pin "35") (pinfunction "P$35_35") (pintype "bidirectional"))
    )
    (net (code "109") (name "unconnected-(U$1-P$37-Pad37)") (class "Default")
      (node (ref "U$1") (pin "37") (pinfunction "P$37_37") (pintype "bidirectional"))
    )
    (net (code "110") (name "unconnected-(U$1-P$38-Pad38)") (class "Default")
      (node (ref "U$1") (pin "38") (pinfunction "P$38_38") (pintype "bidirectional"))
    )
    (net (code "111") (name "unconnected-(U$1-P$39-Pad39)") (class "Default")
      (node (ref "U$1") (pin "39") (pinfunction "P$39_39") (pintype "bidirectional"))
    )
    (net (code "112") (name "unconnected-(U$1-P$40-Pad40)") (class "Default")
      (node (ref "U$1") (pin "40") (pinfunction "P$40_40") (pintype "bidirectional"))
    )
    (net (code "113") (name "unconnected-(U$1-P$41-Pad41)") (class "Default")
      (node (ref "U$1") (pin "41") (pinfunction "P$41_41") (pintype "bidirectional"))
    )
    (net (code "114") (name "unconnected-(U$1-P$42-Pad42)") (class "Default")
      (node (ref "U$1") (pin "42") (pinfunction "P$42_42") (pintype "bidirectional"))
    )
    (net (code "115") (name "unconnected-(U$1-P$50-Pad50)") (class "Default")
      (node (ref "U$1") (pin "50") (pinfunction "P$50_50") (pintype "bidirectional"))
    )
    (net (code "116") (name "unconnected-(U$1-P$51-Pad51)") (class "Default")
      (node (ref "U$1") (pin "51") (pinfunction "P$51_51") (pintype "bidirectional"))
    )
    (net (code "117") (name "unconnected-(U$1-P$52-Pad52)") (class "Default")
      (node (ref "U$1") (pin "52") (pinfunction "P$52_52") (pintype "bidirectional"))
    )
    (net (code "118") (name "unconnected-(U$1-P$53-Pad53)") (class "Default")
      (node (ref "U$1") (pin "53") (pinfunction "P$53_53") (pintype "bidirectional"))
    )
    (net (code "119") (name "unconnected-(U$1-P$58-Pad58)") (class "Default")
      (node (ref "U$1") (pin "58") (pinfunction "P$58_58") (pintype "bidirectional"))
    )
    (net (code "120") (name "unconnected-(U$1-P$59-Pad59)") (class "Default")
      (node (ref "U$1") (pin "59") (pinfunction "P$59_59") (pintype "bidirectional"))
    )
    (net (code "121") (name "unconnected-(U$1-P$60-Pad60)") (class "Default")
      (node (ref "U$1") (pin "60") (pinfunction "P$60_60") (pintype "bidirectional"))
    )
    (net (code "122") (name "unconnected-(U$1-P$62-Pad62)") (class "Default")
      (node (ref "U$1") (pin "62") (pinfunction "P$62_62") (pintype "bidirectional"))
    )
    (net (code "123") (name "unconnected-(U$1-P$63-Pad63)") (class "Default")
      (node (ref "U$1") (pin "63") (pinfunction "P$63_63") (pintype "bidirectional"))
    )
    (net (code "124") (name "unconnected-(U$1-P$64-Pad64)") (class "Default")
      (node (ref "U$1") (pin "64") (pinfunction "P$64_64") (pintype "bidirectional"))
    )
    (net (code "125") (name "unconnected-(U$1-P$65-Pad65)") (class "Default")
      (node (ref "U$1") (pin "65") (pinfunction "P$65_65") (pintype "bidirectional"))
    )
    (net (code "126") (name "unconnected-(U$1-P$66-Pad66)") (class "Default")
      (node (ref "U$1") (pin "66") (pinfunction "P$66_66") (pintype "bidirectional"))
    )
    (net (code "127") (name "unconnected-(U$1-P$67-Pad67)") (class "Default")
      (node (ref "U$1") (pin "67") (pinfunction "P$67_67") (pintype "bidirectional"))
    )
    (net (code "128") (name "unconnected-(U$1-P$68-Pad68)") (class "Default")
      (node (ref "U$1") (pin "68") (pinfunction "P$68_68") (pintype "bidirectional"))
    )
    (net (code "129") (name "unconnected-(U$1-P$69-Pad69)") (class "Default")
      (node (ref "U$1") (pin "69") (pinfunction "P$69_69") (pintype "bidirectional"))
    )
    (net (code "130") (name "unconnected-(U$1-P$70-Pad70)") (class "Default")
      (node (ref "U$1") (pin "70") (pinfunction "P$70_70") (pintype "bidirectional"))
    )
    (net (code "131") (name "unconnected-(U$1-P$71-Pad71)") (class "Default")
      (node (ref "U$1") (pin "71") (pinfunction "P$71_71") (pintype "bidirectional"))
    )
    (net (code "132") (name "unconnected-(U$1-P$72-Pad72)") (class "Default")
      (node (ref "U$1") (pin "72") (pinfunction "P$72_72") (pintype "bidirectional"))
    )
    (net (code "133") (name "unconnected-(U$1-P$73-Pad73)") (class "Default")
      (node (ref "U$1") (pin "73") (pinfunction "P$73_73") (pintype "bidirectional"))
    )
    (net (code "134") (name "unconnected-(U$1-P$85-Pad85)") (class "Default")
      (node (ref "U$1") (pin "85") (pinfunction "P$85_85") (pintype "bidirectional"))
    )
    (net (code "135") (name "unconnected-(U$1-P$86-Pad86)") (class "Default")
      (node (ref "U$1") (pin "86") (pinfunction "P$86_86") (pintype "bidirectional"))
    )
    (net (code "136") (name "unconnected-(U$1-P$87-Pad87)") (class "Default")
      (node (ref "U$1") (pin "87") (pinfunction "P$87_87") (pintype "bidirectional"))
    )
    (net (code "137") (name "unconnected-(U$1-P$88-Pad88)") (class "Default")
      (node (ref "U$1") (pin "88") (pinfunction "P$88_88") (pintype "bidirectional"))
    )
    (net (code "138") (name "unconnected-(U$1-P$90-Pad90)") (class "Default")
      (node (ref "U$1") (pin "90") (pinfunction "P$90_90") (pintype "bidirectional"))
    )
    (net (code "139") (name "unconnected-(U$1-P$91-Pad91)") (class "Default")
      (node (ref "U$1") (pin "91") (pinfunction "P$91_91") (pintype "bidirectional"))
    )
    (net (code "140") (name "unconnected-(U$1-P$92-Pad92)") (class "Default")
      (node (ref "U$1") (pin "92") (pinfunction "P$92_92") (pintype "bidirectional"))
    )
    (net (code "141") (name "unconnected-(U$1-P$107-Pad107)") (class "Default")
      (node (ref "U$1") (pin "107") (pinfunction "P$107_107") (pintype "bidirectional"))
    )
    (net (code "142") (name "unconnected-(U$1-P$108-Pad108)") (class "Default")
      (node (ref "U$1") (pin "108") (pinfunction "P$108_108") (pintype "bidirectional"))
    )
    (net (code "143") (name "unconnected-(U$1-P$109-Pad109)") (class "Default")
      (node (ref "U$1") (pin "109") (pinfunction "P$109_109") (pintype "bidirectional"))
    )
    (net (code "144") (name "unconnected-(U$1-P$110-Pad110)") (class "Default")
      (node (ref "U$1") (pin "110") (pinfunction "P$110_110") (pintype "bidirectional"))
    )
    (net (code "145") (name "unconnected-(U$1-P$111-Pad111)") (class "Default")
      (node (ref "U$1") (pin "111") (pinfunction "P$111_111") (pintype "bidirectional"))
    )
    (net (code "146") (name "unconnected-(U$1-VCC_1V8-Pad77)") (class "Default")
      (node (ref "U$1") (pin "77") (pinfunction "VCC_1V8_77") (pintype "output"))
    )
    (net (code "147") (name "unconnected-(U$1-VCC_3V3-Pad78)") (class "Default")
      (node (ref "U$1") (pin "78") (pinfunction "VCC_3V3_78") (pintype "output"))
    )
    (net (code "148") (name "unconnected-(U2-TS-Pad47)") (class "Default")
      (node (ref "U2") (pin "47") (pinfunction "TS_47") (pintype "input"))
    )
  )
)
